# 00_ESP8266_CH340.net
KiCad netlist of a schematic drawn in Altium Designer
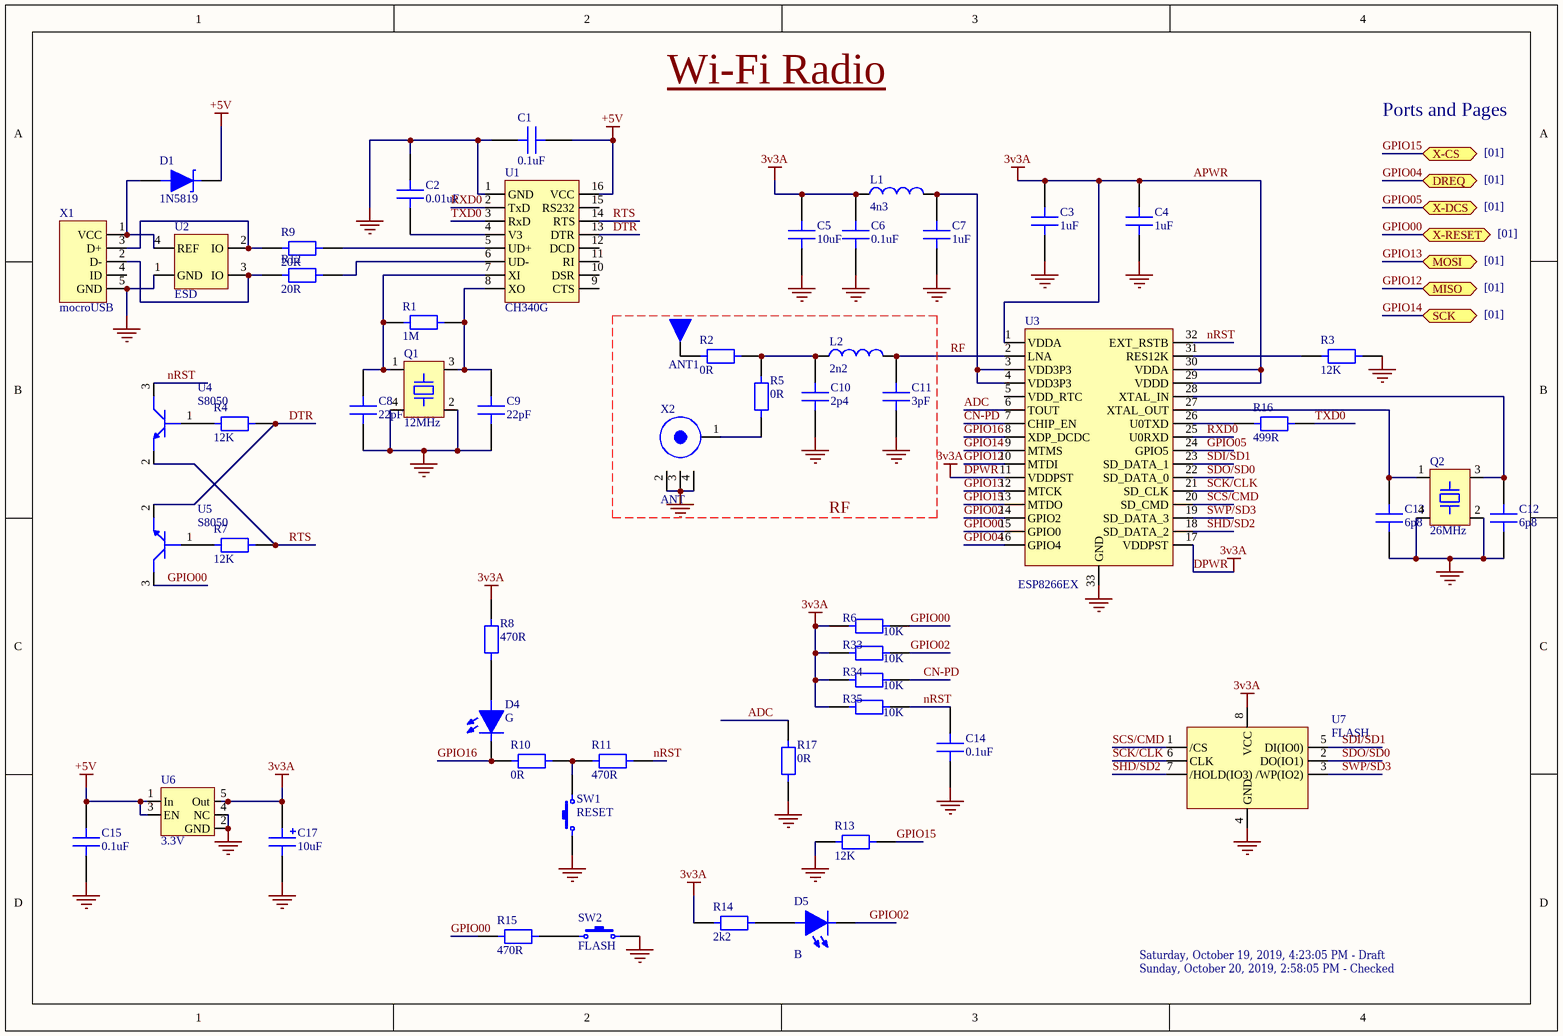
[diagram p0: [00] ESP8266 CH340.SchDoc]

(export (version "E")
  (design (tool "Eeschema 10.0.6"))
  (components
    (comp (ref "ANT1")
      (value "ANT")
      (footprint "PIFA")
      (description "ANT WIFI PCB TRACE ANTENNA 2.4GHz")
      (libsource (lib "WiFi_Lib") (part "ANT WI-FI PCB 2.4GHz"))
    )
    (comp (ref "C1")
      (value "0.1uF")
      (footprint "CAP 0805")
      (description "CAP CER 0.1uF 0805 50V X7R")
      (fields
        (field (name "MANUFACTURER") "Vishay Vitramon")
        (field (name "MANUFACTURER PART NUMBER") "VJ0805Y104KXAAT")
      )
      (libsource (lib "WiFi_Lib") (part "VJ0805Y104KXAAT"))
    )
    (comp (ref "C2")
      (value "0.01uF")
      (footprint "CAP 0603")
      (description "CAP CER 0.01uF 0603 10 nF 50 V ±10 % Tolerance X7R SMT Multilayer Ceramic Chip Capacitor")
      (fields
        (field (name "MANUFACTURER") "Vishay Vitramon")
        (field (name "MANUFACTURER PART NUMBER") "VJ0603Y103KXAAC")
      )
      (libsource (lib "WiFi_Lib") (part "VJ0603Y103KXAAC"))
    )
    (comp (ref "C3")
      (value "1uF")
      (footprint "CAP 0603")
      (description "CAP CER 1uF 0603 16V X7R 10% SMD 125C Paper T/R")
      (fields
        (field (name "MANUFACTURER") "Vishay Semiconductors")
        (field (name "MANUFACTURER PART NUMBER") "VJ0603Y105KXJCW1BC")
      )
      (libsource (lib "WiFi_Lib") (part "VJ0603Y105KXJCW1BC"))
    )
    (comp (ref "C4")
      (value "1uF")
      (footprint "CAP 0603")
      (description "CAP CER 1uF 0603 16V X7R 10% SMD 125C Paper T/R")
      (fields
        (field (name "MANUFACTURER") "Vishay Semiconductors")
        (field (name "MANUFACTURER PART NUMBER") "VJ0603Y105KXJCW1BC")
      )
      (libsource (lib "WiFi_Lib") (part "VJ0603Y105KXJCW1BC"))
    )
    (comp (ref "C5")
      (value "10uF")
      (footprint "CAP 0603")
      (description "CAP CER 10UF 0603 6.3V")
      (fields
        (field (name "MANUFACTURER") "KEMET")
        (field (name "MANUFACTURER PART NUMBER") "C0603C106M9PACTU")
      )
      (libsource (lib "WiFi_Lib") (part "C0603C106M9PACTU"))
    )
    (comp (ref "C6")
      (value "0.1uF")
      (footprint "CAP 0603")
      (description "CAP CER 0.1uF 0603- SMD/SMT .1UF 25V 5% 0603")
      (fields
        (field (name "MANUFACTURER") "Vishay Vitramon")
        (field (name "MANUFACTURER PART NUMBER") "VJ0603Y104JXXAC")
      )
      (libsource (lib "WiFi_Lib") (part "VJ0603Y104JXXAC"))
    )
    (comp (ref "C7")
      (value "1uF")
      (footprint "CAP 0603")
      (description "CAP CER 1uF 0603 16V X7R 10% SMD 125C Paper T/R")
      (fields
        (field (name "MANUFACTURER") "Vishay Semiconductors")
        (field (name "MANUFACTURER PART NUMBER") "VJ0603Y105KXJCW1BC")
      )
      (libsource (lib "WiFi_Lib") (part "VJ0603Y105KXJCW1BC"))
    )
    (comp (ref "C8")
      (value "22pF")
      (footprint "CAP 0603")
      (description "CAP CER 22PF 0603 250V C0G/NP0")
      (fields
        (field (name "MANUFACTURER") "KEMET")
        (field (name "MANUFACTURER PART NUMBER") "CBR06C220JAGAC")
      )
      (libsource (lib "WiFi_Lib") (part "CBR06C220JAGAC"))
    )
    (comp (ref "C9")
      (value "22pF")
      (footprint "CAP 0603")
      (description "CAP CER 22PF 0603 250V C0G/NP0")
      (fields
        (field (name "MANUFACTURER") "KEMET")
        (field (name "MANUFACTURER PART NUMBER") "CBR06C220JAGAC")
      )
      (libsource (lib "WiFi_Lib") (part "CBR06C220JAGAC"))
    )
    (comp (ref "C10")
      (value "2p4")
      (footprint "CAP 0402")
      (description "CAP CER 2.4pF 0402 50V C0G 0.1pF SMD 0402 125°C Paper T/R")
      (fields
        (field (name "MANUFACTURER") "KEMET")
        (field (name "MANUFACTURER PART NUMBER") "CBR04C249B5GAC")
      )
      (libsource (lib "WiFi_Lib") (part "CBR04C249B5GAC"))
    )
    (comp (ref "C11")
      (value "3pF")
      (footprint "CAP 0402")
      (description "CAP CER 3PF 0402 50V NP0")
      (fields
        (field (name "MANUFACTURER") "KEMET")
        (field (name "MANUFACTURER PART NUMBER") "CBR04C309B5GAC")
      )
      (libsource (lib "WiFi_Lib") (part "CBR04C309B5GAC"))
    )
    (comp (ref "C12")
      (value "6p8")
      (footprint "CAP 0603")
      (description "CAP CER 6.8PF 0603 250V C0G/NP0")
      (fields
        (field (name "MANUFACTURER") "KEMET")
        (field (name "MANUFACTURER PART NUMBER") "CBR06C689BAGAC")
      )
      (libsource (lib "WiFi_Lib") (part "CBR06C689BAGAC"))
    )
    (comp (ref "C13")
      (value "6p8")
      (footprint "CAP 0603")
      (description "CAP CER 6.8PF 0603 250V C0G/NP0")
      (fields
        (field (name "MANUFACTURER") "KEMET")
        (field (name "MANUFACTURER PART NUMBER") "CBR06C689BAGAC")
      )
      (libsource (lib "WiFi_Lib") (part "CBR06C689BAGAC"))
    )
    (comp (ref "C14")
      (value "0.1uF")
      (footprint "CAP 0603")
      (description "CAP CER 0.1uF 0603- SMD/SMT .1UF 25V 5% 0603")
      (fields
        (field (name "MANUFACTURER") "Vishay Vitramon")
        (field (name "MANUFACTURER PART NUMBER") "VJ0603Y104JXXAC")
      )
      (libsource (lib "WiFi_Lib") (part "VJ0603Y104JXXAC"))
    )
    (comp (ref "C15")
      (value "0.1uF")
      (footprint "CAP 0805")
      (description "CAP CER 0.1uF 0805 50V X7R")
      (fields
        (field (name "MANUFACTURER") "Vishay Vitramon")
        (field (name "MANUFACTURER PART NUMBER") "VJ0805Y104KXAAT")
      )
      (libsource (lib "WiFi_Lib") (part "VJ0805Y104KXAAT"))
    )
    (comp (ref "C17")
      (value "10uF")
      (footprint "CAP 1206")
      (description "CAP TANT 10UF 1206 6.3V 10%")
      (fields
        (field (name "MANUFACTURER") "Vishay Sprague")
        (field (name "MANUFACTURER PART NUMBER") "293D106X96R3A2TE3")
      )
      (libsource (lib "WiFi_Lib") (part "293D106X96R3A2TE3"))
    )
    (comp (ref "D1")
      (value "1N5819")
      (footprint "SOD123 Diode")
      (description "DIODE SCHOTTKY 40V 1A SOD123")
      (fields (field (name "MANUFACTURER") "Diodes") (field (name "MANUFACTURER PART NUMBER") "1N5819HW-7-F"))
      (libsource (lib "WiFi_Lib") (part "1N5819HW-7-F"))
    )
    (comp (ref "D4")
      (value "G")
      (footprint "LED 0603")
      (description "LED GREEN 0603 574nm 2-Pin Chip LED T/R")
      (fields
        (field (name "MANUFACTURER") "Vishay Lite-On")
        (field (name "MANUFACTURER PART NUMBER") "LTST-C194KGKT")
      )
      (libsource (lib "WiFi_Lib") (part "LTST-C194KGKT"))
    )
    (comp (ref "D5")
      (value "B")
      (footprint "LED 0603")
      (description "LED BLUE 0603 CLEAR CHIP SMD")
      (fields
        (field (name "MANUFACTURER") "Vishay Lite-On")
        (field (name "MANUFACTURER PART NUMBER") "LTST-C193TBKT-5A")
      )
      (libsource (lib "WiFi_Lib") (part "LTST-C193TBKT-5A"))
    )
    (comp (ref "L1")
      (value "4n3")
      (footprint "IND 0603 LQW")
      (description "IND SMD 4.3nH 0603 850mA FIXED 59 MOHM")
      (fields
        (field (name "MANUFACTURER") "Murata")
        (field (name "MANUFACTURER PART NUMBER") "LQW18AN4N3D00D")
      )
      (libsource (lib "WiFi_Lib") (part "LQW18AN4N3D00D"))
    )
    (comp (ref "L2")
      (value "2n2")
      (footprint "IND 0402")
      (description "IND SMD 2.2NH 0402 300MA 160 MOHM")
      (fields
        (field (name "MANUFACTURER") "Johanson")
        (field (name "MANUFACTURER PART NUMBER") "L-07C2N2SV6T")
      )
      (libsource (lib "WiFi_Lib") (part "L-07C2N2SV6T"))
    )
    (comp (ref "Q1")
      (value "12MHz")
      (footprint "ABM8W")
      (description "CRYSTAL SMD 12MHz ±10ppm (Tol) ±10ppm (Stability) 20pF FUND 120Ohm 4-Pin Ultra Mini-CSMD T/R")
      (fields
        (field (name "MANUFACTURER") "Abracon")
        (field (name "MANUFACTURER PART NUMBER") "ABM8-12.000MHZ-20-B1U-T")
      )
      (libsource (lib "WiFi_Lib") (part "ABM8-12.000MHZ-20-B1U-T"))
    )
    (comp (ref "Q2")
      (value "26MHz")
      (footprint "ABM8W")
      (description "CRYSTAL SMD 26MHz 3.2mm ±10ppm (Tol) ±10ppm (Stability) 10pF FUND 50Ohm 4-Pin Ultra Mini-CSMD T/R")
      (fields
        (field (name "MANUFACTURER") "Abracon")
        (field (name "MANUFACTURER PART NUMBER") "ABM8-26.000MHZ-10-1-U-T")
      )
      (libsource (lib "WiFi_Lib") (part "ABM8-26.000MHZ-10-1-U-T"))
    )
    (comp (ref "R1")
      (value "1M")
      (footprint "RES 0603")
      (description "RES SMD 1M 0603 1% 1/10W")
      (fields
        (field (name "MANUFACTURER") "Vishay")
        (field (name "MANUFACTURER PART NUMBER") "CRCW06031M00FKEA")
      )
      (libsource (lib "WiFi_Lib") (part "CRCW06031M00FKEA"))
    )
    (comp (ref "R2")
      (value "0R")
      (footprint "RES 0405 - Jumper")
      (description "RES SMD 0R 0402 JUMPER 1/16W")
      (fields
        (field (name "MANUFACTURER") "Vishay")
        (field (name "MANUFACTURER PART NUMBER") "CRCW04020000Z0ED")
      )
      (libsource (lib "WiFi_Lib") (part "CRCW04020000Z0ED"))
    )
    (comp (ref "R3")
      (value "12K")
      (footprint "RES 0603")
      (description "RES SMD 12K 0603 1% 1/10W")
      (fields
        (field (name "MANUFACTURER") "Vishay")
        (field (name "MANUFACTURER PART NUMBER") "CRCW060312K0FKEAC")
      )
      (libsource (lib "WiFi_Lib") (part "CRCW060312K0FKEAC"))
    )
    (comp (ref "R4")
      (value "12K")
      (footprint "RES 0603")
      (description "RES SMD 12K 0603 1% 1/10W")
      (fields
        (field (name "MANUFACTURER") "Vishay")
        (field (name "MANUFACTURER PART NUMBER") "CRCW060312K0FKEAC")
      )
      (libsource (lib "WiFi_Lib") (part "CRCW060312K0FKEAC"))
    )
    (comp (ref "R5")
      (value "0R")
      (footprint "RES 0405 - Jumper")
      (description "RES SMD 0R 0402 JUMPER 1/16W")
      (fields
        (field (name "MANUFACTURER") "Vishay")
        (field (name "MANUFACTURER PART NUMBER") "CRCW04020000Z0ED")
      )
      (libsource (lib "WiFi_Lib") (part "CRCW04020000Z0ED"))
    )
    (comp (ref "R6")
      (value "10K")
      (footprint "RES 0603")
      (description "RES SMD 10K 0603 1% 1/10W")
      (fields
        (field (name "MANUFACTURER") "Vishay")
        (field (name "MANUFACTURER PART NUMBER") "CRCW060310K0FKEA")
      )
      (libsource (lib "WiFi_Lib") (part "CRCW060310K0FKEA"))
    )
    (comp (ref "R7")
      (value "12K")
      (footprint "RES 0603")
      (description "RES SMD 12K 0603 1% 1/10W")
      (fields
        (field (name "MANUFACTURER") "Vishay")
        (field (name "MANUFACTURER PART NUMBER") "CRCW060312K0FKEAC")
      )
      (libsource (lib "WiFi_Lib") (part "CRCW060312K0FKEAC"))
    )
    (comp (ref "R8")
      (value "470R")
      (footprint "RES 0603")
      (description "RES SMD 470 0603 1% 1/10W")
      (fields
        (field (name "MANUFACTURER") "Vishay")
        (field (name "MANUFACTURER PART NUMBER") "CRCW0603470RFKEAC")
      )
      (libsource (lib "WiFi_Lib") (part "CRCW0603470RFKEAC"))
    )
    (comp (ref "R9")
      (value "20R")
      (footprint "RES 0603")
      (description "RES SMD 20 0603 1% 1/4W")
      (fields
        (field (name "MANUFACTURER") "Vishay Dale")
        (field (name "MANUFACTURER PART NUMBER") "CRCW060320R0FKEAHP")
      )
      (libsource (lib "WiFi_Lib") (part "CRCW060320R0FKEAHP"))
    )
    (comp (ref "R10")
      (value "0R")
      (footprint "RES 0603 - Jumper")
      (description "RES SMD 0R 0603 JUMPER PU=5000 ST, CRCW06030000Z0EA, Vishay")
      (fields
        (field (name "MANUFACTURER") "Vishay")
        (field (name "MANUFACTURER PART NUMBER") "CRCW0603-0000Z0EA")
      )
      (libsource (lib "WiFi_Lib") (part "CRCW0603-0000Z0EA"))
    )
    (comp (ref "R11")
      (value "470R")
      (footprint "RES 0603")
      (description "RES SMD 470 0603 1% 1/10W")
      (fields
        (field (name "MANUFACTURER") "Vishay")
        (field (name "MANUFACTURER PART NUMBER") "CRCW0603470RFKEAC")
      )
      (libsource (lib "WiFi_Lib") (part "CRCW0603470RFKEAC"))
    )
    (comp (ref "R12")
      (value "20R")
      (footprint "RES 0603")
      (description "RES SMD 20 0603 1% 1/4W")
      (fields
        (field (name "MANUFACTURER") "Vishay Dale")
        (field (name "MANUFACTURER PART NUMBER") "CRCW060320R0FKEAHP")
      )
      (libsource (lib "WiFi_Lib") (part "CRCW060320R0FKEAHP"))
    )
    (comp (ref "R13")
      (value "12K")
      (footprint "RES 0603")
      (description "RES SMD 12K 0603 1% 1/10W")
      (fields
        (field (name "MANUFACTURER") "Vishay")
        (field (name "MANUFACTURER PART NUMBER") "CRCW060312K0FKEAC")
      )
      (libsource (lib "WiFi_Lib") (part "CRCW060312K0FKEAC"))
    )
    (comp (ref "R14")
      (value "2k2")
      (footprint "RES 0603")
      (description "RES SMD 2.2K 0603 1% 1/10W")
      (fields
        (field (name "MANUFACTURER") "Vishay Semiconductors")
        (field (name "MANUFACTURER PART NUMBER") "CRCW06032K20FKEAC")
      )
      (libsource (lib "WiFi_Lib") (part "CRCW06032K20FKEAC"))
    )
    (comp (ref "R15")
      (value "470R")
      (footprint "RES 0603")
      (description "RES SMD 470 0603 1% 1/10W")
      (fields
        (field (name "MANUFACTURER") "Vishay")
        (field (name "MANUFACTURER PART NUMBER") "CRCW0603470RFKEAC")
      )
      (libsource (lib "WiFi_Lib") (part "CRCW0603470RFKEAC"))
    )
    (comp (ref "R16")
      (value "499R")
      (footprint "RES 0603")
      (description "RES SMD 499 0603 1% 1/4W")
      (fields
        (field (name "MANUFACTURER") "Vishay Dale")
        (field (name "MANUFACTURER PART NUMBER") "CRCW0603499RFKEAHP")
      )
      (libsource (lib "WiFi_Lib") (part "CRCW0603499RFKEAHP"))
    )
    (comp (ref "R17")
      (value "0R")
      (footprint "RES 0603 - Jumper")
      (description "RES SMD 0R 0603 JUMPER PU=5000 ST, CRCW06030000Z0EA, Vishay")
      (fields
        (field (name "MANUFACTURER") "Vishay")
        (field (name "MANUFACTURER PART NUMBER") "CRCW0603-0000Z0EA")
      )
      (libsource (lib "WiFi_Lib") (part "CRCW0603-0000Z0EA"))
    )
    (comp (ref "R33")
      (value "10K")
      (footprint "RES 0603")
      (description "RES SMD 10K 0603 1% 1/10W")
      (fields
        (field (name "MANUFACTURER") "Vishay")
        (field (name "MANUFACTURER PART NUMBER") "CRCW060310K0FKEA")
      )
      (libsource (lib "WiFi_Lib") (part "CRCW060310K0FKEA"))
    )
    (comp (ref "R34")
      (value "10K")
      (footprint "RES 0603")
      (description "RES SMD 10K 0603 1% 1/10W")
      (fields
        (field (name "MANUFACTURER") "Vishay")
        (field (name "MANUFACTURER PART NUMBER") "CRCW060310K0FKEA")
      )
      (libsource (lib "WiFi_Lib") (part "CRCW060310K0FKEA"))
    )
    (comp (ref "R35")
      (value "10K")
      (footprint "RES 0603")
      (description "RES SMD 10K 0603 1% 1/10W")
      (fields
        (field (name "MANUFACTURER") "Vishay")
        (field (name "MANUFACTURER PART NUMBER") "CRCW060310K0FKEA")
      )
      (libsource (lib "WiFi_Lib") (part "CRCW060310K0FKEA"))
    )
    (comp (ref "SW1")
      (value "RESET")
      (footprint "SWITCH MICRO")
      (description "SWITCH TACT SPST-NO 0.05A 12V")
      (fields
        (field (name "MANUFACTURER") "ITT C&K")
        (field (name "MANUFACTURER PART NUMBER") "PTS820J25MSMTRLFS")
      )
      (libsource (lib "WiFi_Lib") (part "PTS820J25MSMTRLFS"))
    )
    (comp (ref "SW2")
      (value "FLASH")
      (footprint "SWITCH MICRO")
      (description "SWITCH TACT SPST-NO 0.05A 12V")
      (fields
        (field (name "MANUFACTURER") "ITT C&K")
        (field (name "MANUFACTURER PART NUMBER") "PTS820J25MSMTRLFS")
      )
      (libsource (lib "WiFi_Lib") (part "PTS820J25MSMTRLFS"))
    )
    (comp (ref "U1")
      (value "CH340G")
      (footprint "SOP-16")
      (description "IC CH340G USB to serial chip")
      (libsource (lib "WiFi_Lib") (part "IC CH340G USB to serial chip"))
    )
    (comp (ref "U2")
      (value "ESD")
      (footprint "SOT143")
      (description "TVS DIODE 5V 20V SOT143")
      (fields (field (name "MANUFACTURER") "Bourns") (field (name "MANUFACTURER PART NUMBER") "CD143A-SR05"))
      (libsource (lib "WiFi_Lib") (part "CD143A-SR05"))
    )
    (comp (ref "U3")
      (value "ESP8266EX")
      (footprint "QFN-32 Thermal")
      (description "IC ESP8266EX, QFN32-PIN, 5_5")
      (fields (field (name "MANUFACTURER") "Espressif Systems"))
      (libsource (lib "WiFi_Lib") (part "ESP8266EX"))
    )
    (comp (ref "U4")
      (value "S8050")
      (footprint "SOT-23")
      (description "TRANS NPN 25V 1.5A SOT23")
      (fields (field (name "MANUFACTURER") "MCC") (field (name "MANUFACTURER PART NUMBER") "MMSS8050-H-TP"))
      (libsource (lib "WiFi_Lib") (part "MMSS8050-H-TP"))
    )
    (comp (ref "U5")
      (value "S8050")
      (footprint "SOT-23")
      (description "TRANS NPN 25V 1.5A SOT23")
      (fields (field (name "MANUFACTURER") "MCC") (field (name "MANUFACTURER PART NUMBER") "MMSS8050-H-TP"))
      (libsource (lib "WiFi_Lib") (part "MMSS8050-H-TP"))
    )
    (comp (ref "U6")
      (value "3.3V")
      (footprint "SOT-23-5")
      (description "IC REG LIN 3.3V 300mALow IQLDO Reg")
      (fields
        (field (name "MANUFACTURER") "Texas Instruments")
        (field (name "MANUFACTURER PART NUMBER") "TLV70233DBVR")
      )
      (libsource (lib "WiFi_Lib") (part "TLV70233DBVR"))
    )
    (comp (ref "U7")
      (value "FLASH")
      (footprint "SOIC-8 208-mil")
      (description "IC FLASH 32M SPI 133MHZ 8SOIC")
      (fields
        (field (name "MANUFACTURER") "Winbond")
        (field (name "MANUFACTURER PART NUMBER") "W25Q32JVSSIQTR")
      )
      (libsource (lib "WiFi_Lib") (part "W25Q32JVSSIQTR"))
    )
    (comp (ref "X1")
      (value "mocroUSB")
      (footprint "microUSB")
      (description "CONN USB Type B RCP 5 POS 0.65mm Solder RA Thru-Hole 5 Terminal 1 Port Embossed T/R")
      (fields (field (name "MANUFACTURER") "Molex") (field (name "MANUFACTURER PART NUMBER") "105017-1001"))
      (libsource (lib "WiFi_Lib") (part "105017-1001"))
    )
    (comp (ref "X2")
      (value "ANT")
      (footprint "U.FL Connector")
      (description "CONN U.FL 50OHM MOLEX 73412-0110 RF COAXIAL, MICROCOAXIAL, JACK")
      (fields (field (name "MANUFACTURER") "Molex") (field (name "MANUFACTURER PART NUMBER") "73412-0110"))
      (libsource (lib "WiFi_Lib") (part "73412-0110"))
    )
  )
  (nets
    (net (code "1") (name "+5V") (class "Default")
      (node (ref "C1") (pin "2") (pinfunction "2_2") (pintype "passive"))
      (node (ref "C15") (pin "2") (pinfunction "2_2") (pintype "passive"))
      (node (ref "D1") (pin "2") (pinfunction "2_2") (pintype "passive"))
      (node (ref "U1") (pin "16") (pinfunction "VCC_16") (pintype "passive"))
      (node (ref "U6") (pin "1") (pinfunction "In_1") (pintype "passive"))
      (node (ref "U6") (pin "3") (pinfunction "EN_3") (pintype "passive"))
    )
    (net (code "2") (name "/ADC") (class "Default")
      (node (ref "R17") (pin "2") (pinfunction "2_2") (pintype "passive"))
      (node (ref "U3") (pin "6") (pinfunction "TOUT_6") (pintype "passive"))
    )
    (net (code "3") (name "/CN-PD") (class "Default")
      (node (ref "R34") (pin "2") (pinfunction "2_2") (pintype "passive"))
      (node (ref "U3") (pin "7") (pinfunction "CHIP_EN_7") (pintype "passive"))
    )
    (net (code "4") (name "/DTR") (class "Default")
      (node (ref "R4") (pin "2") (pinfunction "2_2") (pintype "passive"))
      (node (ref "U1") (pin "13") (pinfunction "DTR_13") (pintype "passive"))
      (node (ref "U5") (pin "2") (pinfunction "2_2") (pintype "passive"))
    )
    (net (code "5") (name "/GPIO00") (class "Default")
      (node (ref "R15") (pin "1") (pinfunction "1_1") (pintype "passive"))
      (node (ref "R6") (pin "2") (pinfunction "2_2") (pintype "passive"))
      (node (ref "U3") (pin "15") (pinfunction "GPIO0_15") (pintype "passive"))
      (node (ref "U5") (pin "3") (pinfunction "3_3") (pintype "passive"))
    )
    (net (code "6") (name "/GPIO02") (class "Default")
      (node (ref "D5") (pin "2") (pinfunction "2_2") (pintype "passive"))
      (node (ref "R33") (pin "2") (pinfunction "2_2") (pintype "passive"))
      (node (ref "U3") (pin "14") (pinfunction "GPIO2_14") (pintype "passive"))
    )
    (net (code "7") (name "/GPIO04") (class "Default")
      (node (ref "U3") (pin "16") (pinfunction "GPIO4_16") (pintype "passive"))
    )
    (net (code "8") (name "/GPIO05") (class "Default")
      (node (ref "U3") (pin "24") (pinfunction "GPIO5_24") (pintype "passive"))
    )
    (net (code "9") (name "/GPIO12") (class "Default")
      (node (ref "U3") (pin "10") (pinfunction "MTDI_10") (pintype "passive"))
    )
    (net (code "10") (name "/GPIO13") (class "Default")
      (node (ref "U3") (pin "12") (pinfunction "MTCK_12") (pintype "passive"))
    )
    (net (code "11") (name "/GPIO14") (class "Default")
      (node (ref "U3") (pin "9") (pinfunction "MTMS_9") (pintype "passive"))
    )
    (net (code "12") (name "/GPIO15") (class "Default")
      (node (ref "R13") (pin "2") (pinfunction "2_2") (pintype "passive"))
      (node (ref "U3") (pin "13") (pinfunction "MTDO_13") (pintype "passive"))
    )
    (net (code "13") (name "/GPIO16") (class "Default")
      (node (ref "D4") (pin "2") (pinfunction "2_2") (pintype "passive"))
      (node (ref "R10") (pin "1") (pinfunction "1_1") (pintype "passive"))
      (node (ref "U3") (pin "8") (pinfunction "XDP_DCDC_8") (pintype "passive"))
    )
    (net (code "14") (name "/RF") (class "Default")
      (node (ref "C11") (pin "2") (pinfunction "2_2") (pintype "passive"))
      (node (ref "L2") (pin "2") (pinfunction "2_2") (pintype "passive"))
      (node (ref "U3") (pin "2") (pinfunction "LNA_2") (pintype "passive"))
    )
    (net (code "15") (name "/RTS") (class "Default")
      (node (ref "R7") (pin "2") (pinfunction "2_2") (pintype "passive"))
      (node (ref "U1") (pin "14") (pinfunction "RTS_14") (pintype "passive"))
      (node (ref "U4") (pin "2") (pinfunction "2_2") (pintype "passive"))
    )
    (net (code "16") (name "/RXD0") (class "Default")
      (node (ref "U1") (pin "2") (pinfunction "TxD_2") (pintype "passive"))
      (node (ref "U3") (pin "25") (pinfunction "U0RXD_25") (pintype "passive"))
    )
    (net (code "17") (name "/SCK{slash}CLK") (class "Default")
      (node (ref "U3") (pin "21") (pinfunction "SD_CLK_21") (pintype "passive"))
      (node (ref "U7") (pin "6") (pinfunction "CLK_6") (pintype "passive"))
    )
    (net (code "18") (name "/SCS{slash}CMD") (class "Default")
      (node (ref "U3") (pin "20") (pinfunction "SD_CMD_20") (pintype "passive"))
      (node (ref "U7") (pin "1") (pinfunction "/CS_1") (pintype "passive"))
    )
    (net (code "19") (name "/SDI{slash}SD1") (class "Default")
      (node (ref "U3") (pin "23") (pinfunction "SD_DATA_1_23") (pintype "passive"))
      (node (ref "U7") (pin "5") (pinfunction "DI(IO0)_5") (pintype "passive"))
    )
    (net (code "20") (name "/SDO{slash}SD0") (class "Default")
      (node (ref "U3") (pin "22") (pinfunction "SD_DATA_0_22") (pintype "passive"))
      (node (ref "U7") (pin "2") (pinfunction "DO(IO1)_2") (pintype "passive"))
    )
    (net (code "21") (name "/SHD{slash}SD2") (class "Default")
      (node (ref "U3") (pin "18") (pinfunction "SD_DATA_2_18") (pintype "passive"))
      (node (ref "U7") (pin "7") (pinfunction "/HOLD(IO3)_7") (pintype "passive"))
    )
    (net (code "22") (name "/SWP{slash}SD3") (class "Default")
      (node (ref "U3") (pin "19") (pinfunction "SD_DATA_3_19") (pintype "passive"))
      (node (ref "U7") (pin "3") (pinfunction "/WP(IO2)_3") (pintype "passive"))
    )
    (net (code "23") (name "/TXD0") (class "Default")
      (node (ref "R16") (pin "2") (pinfunction "2_2") (pintype "passive"))
      (node (ref "U1") (pin "3") (pinfunction "RxD_3") (pintype "passive"))
    )
    (net (code "24") (name "/nRST") (class "Default")
      (node (ref "C14") (pin "2") (pinfunction "2_2") (pintype "passive"))
      (node (ref "R11") (pin "2") (pinfunction "2_2") (pintype "passive"))
      (node (ref "R35") (pin "2") (pinfunction "2_2") (pintype "passive"))
      (node (ref "U3") (pin "32") (pinfunction "EXT_RSTB_32") (pintype "passive"))
      (node (ref "U4") (pin "3") (pinfunction "3_3") (pintype "passive"))
    )
    (net (code "25") (name "3v3A") (class "Default")
      (node (ref "C17") (pin "1") (pinfunction "1_1") (pintype "passive"))
      (node (ref "C3") (pin "2") (pinfunction "2_2") (pintype "passive"))
      (node (ref "C4") (pin "2") (pinfunction "2_2") (pintype "passive"))
      (node (ref "C5") (pin "2") (pinfunction "2_2") (pintype "passive"))
      (node (ref "C6") (pin "2") (pinfunction "2_2") (pintype "passive"))
      (node (ref "L1") (pin "1") (pinfunction "1_1") (pintype "passive"))
      (node (ref "R14") (pin "1") (pinfunction "1_1") (pintype "passive"))
      (node (ref "R33") (pin "1") (pinfunction "1_1") (pintype "passive"))
      (node (ref "R34") (pin "1") (pinfunction "1_1") (pintype "passive"))
      (node (ref "R35") (pin "1") (pinfunction "1_1") (pintype "passive"))
      (node (ref "R6") (pin "1") (pinfunction "1_1") (pintype "passive"))
      (node (ref "R8") (pin "2") (pinfunction "2_2") (pintype "passive"))
      (node (ref "U3") (pin "1") (pinfunction "VDDA_1") (pintype "passive"))
      (node (ref "U3") (pin "11") (pinfunction "VDDPST_11") (pintype "passive"))
      (node (ref "U3") (pin "17") (pinfunction "VDDPST_17") (pintype "passive"))
      (node (ref "U3") (pin "29") (pinfunction "VDDD_29") (pintype "passive"))
      (node (ref "U3") (pin "30") (pinfunction "VDDA_30") (pintype "passive"))
      (node (ref "U6") (pin "5") (pinfunction "Out_5") (pintype "passive"))
      (node (ref "U7") (pin "8") (pinfunction "VCC_8") (pintype "passive"))
    )
    (net (code "26") (name "GND") (class "Default")
      (node (ref "C1") (pin "1") (pinfunction "1_1") (pintype "passive"))
      (node (ref "C10") (pin "1") (pinfunction "1_1") (pintype "passive"))
      (node (ref "C11") (pin "1") (pinfunction "1_1") (pintype "passive"))
      (node (ref "C12") (pin "1") (pinfunction "1_1") (pintype "passive"))
      (node (ref "C13") (pin "1") (pinfunction "1_1") (pintype "passive"))
      (node (ref "C14") (pin "1") (pinfunction "1_1") (pintype "passive"))
      (node (ref "C15") (pin "1") (pinfunction "1_1") (pintype "passive"))
      (node (ref "C17") (pin "2") (pinfunction "2_2") (pintype "passive"))
      (node (ref "C2") (pin "2") (pinfunction "2_2") (pintype "passive"))
      (node (ref "C3") (pin "1") (pinfunction "1_1") (pintype "passive"))
      (node (ref "C4") (pin "1") (pinfunction "1_1") (pintype "passive"))
      (node (ref "C5") (pin "1") (pinfunction "1_1") (pintype "passive"))
      (node (ref "C6") (pin "1") (pinfunction "1_1") (pintype "passive"))
      (node (ref "C7") (pin "1") (pinfunction "1_1") (pintype "passive"))
      (node (ref "C8") (pin "1") (pinfunction "1_1") (pintype "passive"))
      (node (ref "C9") (pin "1") (pinfunction "1_1") (pintype "passive"))
      (node (ref "Q1") (pin "2") (pinfunction "GND_2") (pintype "passive"))
      (node (ref "Q1") (pin "4") (pinfunction "GND_4") (pintype "passive"))
      (node (ref "Q2") (pin "2") (pinfunction "GND_2") (pintype "passive"))
      (node (ref "Q2") (pin "4") (pinfunction "GND_4") (pintype "passive"))
      (node (ref "R13") (pin "1") (pinfunction "1_1") (pintype "passive"))
      (node (ref "R17") (pin "1") (pinfunction "1_1") (pintype "passive"))
      (node (ref "R3") (pin "2") (pinfunction "2_2") (pintype "passive"))
      (node (ref "SW1") (pin "1") (pinfunction "1_1") (pintype "passive"))
      (node (ref "SW2") (pin "2") (pinfunction "2_2") (pintype "passive"))
      (node (ref "U1") (pin "1") (pinfunction "GND_1") (pintype "passive"))
      (node (ref "U2") (pin "1") (pinfunction "GND_1") (pintype "passive"))
      (node (ref "U3") (pin "33") (pinfunction "GND_33") (pintype "passive"))
      (node (ref "U6") (pin "2") (pinfunction "GND_2") (pintype "passive"))
      (node (ref "U6") (pin "4") (pinfunction "NC_4") (pintype "passive"))
      (node (ref "U7") (pin "4") (pinfunction "GND_4") (pintype "passive"))
      (node (ref "X1") (pin "5") (pinfunction "GND_5") (pintype "passive"))
      (node (ref "X2") (pin "2") (pinfunction "2_2") (pintype "passive"))
      (node (ref "X2") (pin "3") (pinfunction "GND_3") (pintype "passive"))
      (node (ref "X2") (pin "4") (pinfunction "4_4") (pintype "passive"))
    )
    (net (code "27") (name "Net-(ANT1-Pad1)") (class "Default")
      (node (ref "ANT1") (pin "1") (pinfunction "1_1") (pintype "passive"))
      (node (ref "R2") (pin "1") (pinfunction "1_1") (pintype "passive"))
    )
    (net (code "28") (name "Net-(C7-Pad2)") (class "Default")
      (node (ref "C7") (pin "2") (pinfunction "2_2") (pintype "passive"))
      (node (ref "L1") (pin "2") (pinfunction "2_2") (pintype "passive"))
      (node (ref "U3") (pin "3") (pinfunction "VDD3P3_3") (pintype "passive"))
      (node (ref "U3") (pin "4") (pinfunction "VDD3P3_4") (pintype "passive"))
    )
    (net (code "29") (name "Net-(C10-Pad2)") (class "Default")
      (node (ref "C10") (pin "2") (pinfunction "2_2") (pintype "passive"))
      (node (ref "L2") (pin "1") (pinfunction "1_1") (pintype "passive"))
      (node (ref "R2") (pin "2") (pinfunction "2_2") (pintype "passive"))
      (node (ref "R5") (pin "2") (pinfunction "2_2") (pintype "passive"))
    )
    (net (code "30") (name "Net-(D4-Pad1)") (class "Default")
      (node (ref "D4") (pin "1") (pinfunction "1_1") (pintype "passive"))
      (node (ref "R8") (pin "1") (pinfunction "1_1") (pintype "passive"))
    )
    (net (code "31") (name "Net-(D5-Pad1)") (class "Default")
      (node (ref "D5") (pin "1") (pinfunction "1_1") (pintype "passive"))
      (node (ref "R14") (pin "2") (pinfunction "2_2") (pintype "passive"))
    )
    (net (code "32") (name "Net-(R4-Pad1)") (class "Default")
      (node (ref "R4") (pin "1") (pinfunction "1_1") (pintype "passive"))
      (node (ref "U4") (pin "1") (pinfunction "1_1") (pintype "passive"))
    )
    (net (code "33") (name "Net-(R5-Pad1)") (class "Default")
      (node (ref "R5") (pin "1") (pinfunction "1_1") (pintype "passive"))
      (node (ref "X2") (pin "1") (pinfunction "1_1") (pintype "passive"))
    )
    (net (code "34") (name "Net-(R7-Pad1)") (class "Default")
      (node (ref "R7") (pin "1") (pinfunction "1_1") (pintype "passive"))
      (node (ref "U5") (pin "1") (pinfunction "1_1") (pintype "passive"))
    )
    (net (code "35") (name "Net-(R10-Pad2)") (class "Default")
      (node (ref "R10") (pin "2") (pinfunction "2_2") (pintype "passive"))
      (node (ref "R11") (pin "1") (pinfunction "1_1") (pintype "passive"))
      (node (ref "SW1") (pin "2") (pinfunction "2_2") (pintype "passive"))
    )
    (net (code "36") (name "Net-(R15-Pad2)") (class "Default")
      (node (ref "R15") (pin "2") (pinfunction "2_2") (pintype "passive"))
      (node (ref "SW2") (pin "1") (pinfunction "1_1") (pintype "passive"))
    )
    (net (code "37") (name "Net-(U1-UD+)") (class "Default")
      (node (ref "R9") (pin "2") (pinfunction "2_2") (pintype "passive"))
      (node (ref "U1") (pin "5") (pinfunction "UD+_5") (pintype "passive"))
    )
    (net (code "38") (name "Net-(U1-UD-)") (class "Default")
      (node (ref "R12") (pin "2") (pinfunction "2_2") (pintype "passive"))
      (node (ref "U1") (pin "6") (pinfunction "UD-_6") (pintype "passive"))
    )
    (net (code "39") (name "Net-(U1-V3)") (class "Default")
      (node (ref "C2") (pin "1") (pinfunction "1_1") (pintype "passive"))
      (node (ref "U1") (pin "4") (pinfunction "V3_4") (pintype "passive"))
    )
    (net (code "40") (name "Net-(U1-XI)") (class "Default")
      (node (ref "C8") (pin "2") (pinfunction "2_2") (pintype "passive"))
      (node (ref "Q1") (pin "1") (pinfunction "1_1") (pintype "passive"))
      (node (ref "R1") (pin "1") (pinfunction "1_1") (pintype "passive"))
      (node (ref "U1") (pin "7") (pinfunction "XI_7") (pintype "passive"))
    )
    (net (code "41") (name "Net-(U1-XO)") (class "Default")
      (node (ref "C9") (pin "2") (pinfunction "2_2") (pintype "passive"))
      (node (ref "Q1") (pin "3") (pinfunction "3_3") (pintype "passive"))
      (node (ref "R1") (pin "2") (pinfunction "2_2") (pintype "passive"))
      (node (ref "U1") (pin "8") (pinfunction "XO_8") (pintype "passive"))
    )
    (net (code "42") (name "Net-(U2-REF)") (class "Default")
      (node (ref "D1") (pin "1") (pinfunction "1_1") (pintype "passive"))
      (node (ref "U2") (pin "4") (pinfunction "REF_4") (pintype "passive"))
      (node (ref "X1") (pin "1") (pinfunction "VCC_1") (pintype "passive"))
    )
    (net (code "43") (name "Net-(U3-RES12K)") (class "Default")
      (node (ref "R3") (pin "1") (pinfunction "1_1") (pintype "passive"))
      (node (ref "U3") (pin "31") (pinfunction "RES12K_31") (pintype "passive"))
    )
    (net (code "44") (name "Net-(U3-U0TXD)") (class "Default")
      (node (ref "R16") (pin "1") (pinfunction "1_1") (pintype "passive"))
      (node (ref "U3") (pin "26") (pinfunction "U0TXD_26") (pintype "passive"))
    )
    (net (code "45") (name "Net-(U3-XTAL_IN)") (class "Default")
      (node (ref "C12") (pin "2") (pinfunction "2_2") (pintype "passive"))
      (node (ref "Q2") (pin "3") (pinfunction "3_3") (pintype "passive"))
      (node (ref "U3") (pin "28") (pinfunction "XTAL_IN_28") (pintype "passive"))
    )
    (net (code "46") (name "Net-(U3-XTAL_OUT)") (class "Default")
      (node (ref "C13") (pin "2") (pinfunction "2_2") (pintype "passive"))
      (node (ref "Q2") (pin "1") (pinfunction "1_1") (pintype "passive"))
      (node (ref "U3") (pin "27") (pinfunction "XTAL_OUT_27") (pintype "passive"))
    )
    (net (code "47") (name "Net-(X1-D+)") (class "Default")
      (node (ref "R9") (pin "1") (pinfunction "1_1") (pintype "passive"))
      (node (ref "U2") (pin "2") (pinfunction "IO_2") (pintype "passive"))
      (node (ref "X1") (pin "3") (pinfunction "D+_3") (pintype "passive"))
    )
    (net (code "48") (name "Net-(X1-D-)") (class "Default")
      (node (ref "R12") (pin "1") (pinfunction "1_1") (pintype "passive"))
      (node (ref "U2") (pin "3") (pinfunction "IO_3") (pintype "passive"))
      (node (ref "X1") (pin "2") (pinfunction "D-_2") (pintype "passive"))
    )
    (net (code "49") (name "unconnected-(U1-CTS-Pad9)") (class "Default")
      (node (ref "U1") (pin "9") (pinfunction "CTS_9") (pintype "passive"))
    )
    (net (code "50") (name "unconnected-(U1-DCD-Pad12)") (class "Default")
      (node (ref "U1") (pin "12") (pinfunction "DCD_12") (pintype "passive"))
    )
    (net (code "51") (name "unconnected-(U1-DSR-Pad10)") (class "Default")
      (node (ref "U1") (pin "10") (pinfunction "DSR_10") (pintype "passive"))
    )
    (net (code "52") (name "unconnected-(U1-RI-Pad11)") (class "Default")
      (node (ref "U1") (pin "11") (pinfunction "RI_11") (pintype "passive"))
    )
    (net (code "53") (name "unconnected-(U1-RS232-Pad15)") (class "Default")
      (node (ref "U1") (pin "15") (pinfunction "RS232_15") (pintype "passive"))
    )
    (net (code "54") (name "unconnected-(U3-VDD_RTC-Pad5)") (class "Default")
      (node (ref "U3") (pin "5") (pinfunction "VDD_RTC_5") (pintype "passive"))
    )
    (net (code "55") (name "unconnected-(X1-ID-Pad4)") (class "Default")
      (node (ref "X1") (pin "4") (pinfunction "ID_4") (pintype "passive"))
    )
  )
)
